# logic.net
KiCad netlist of a schematic drawn in EAGLE
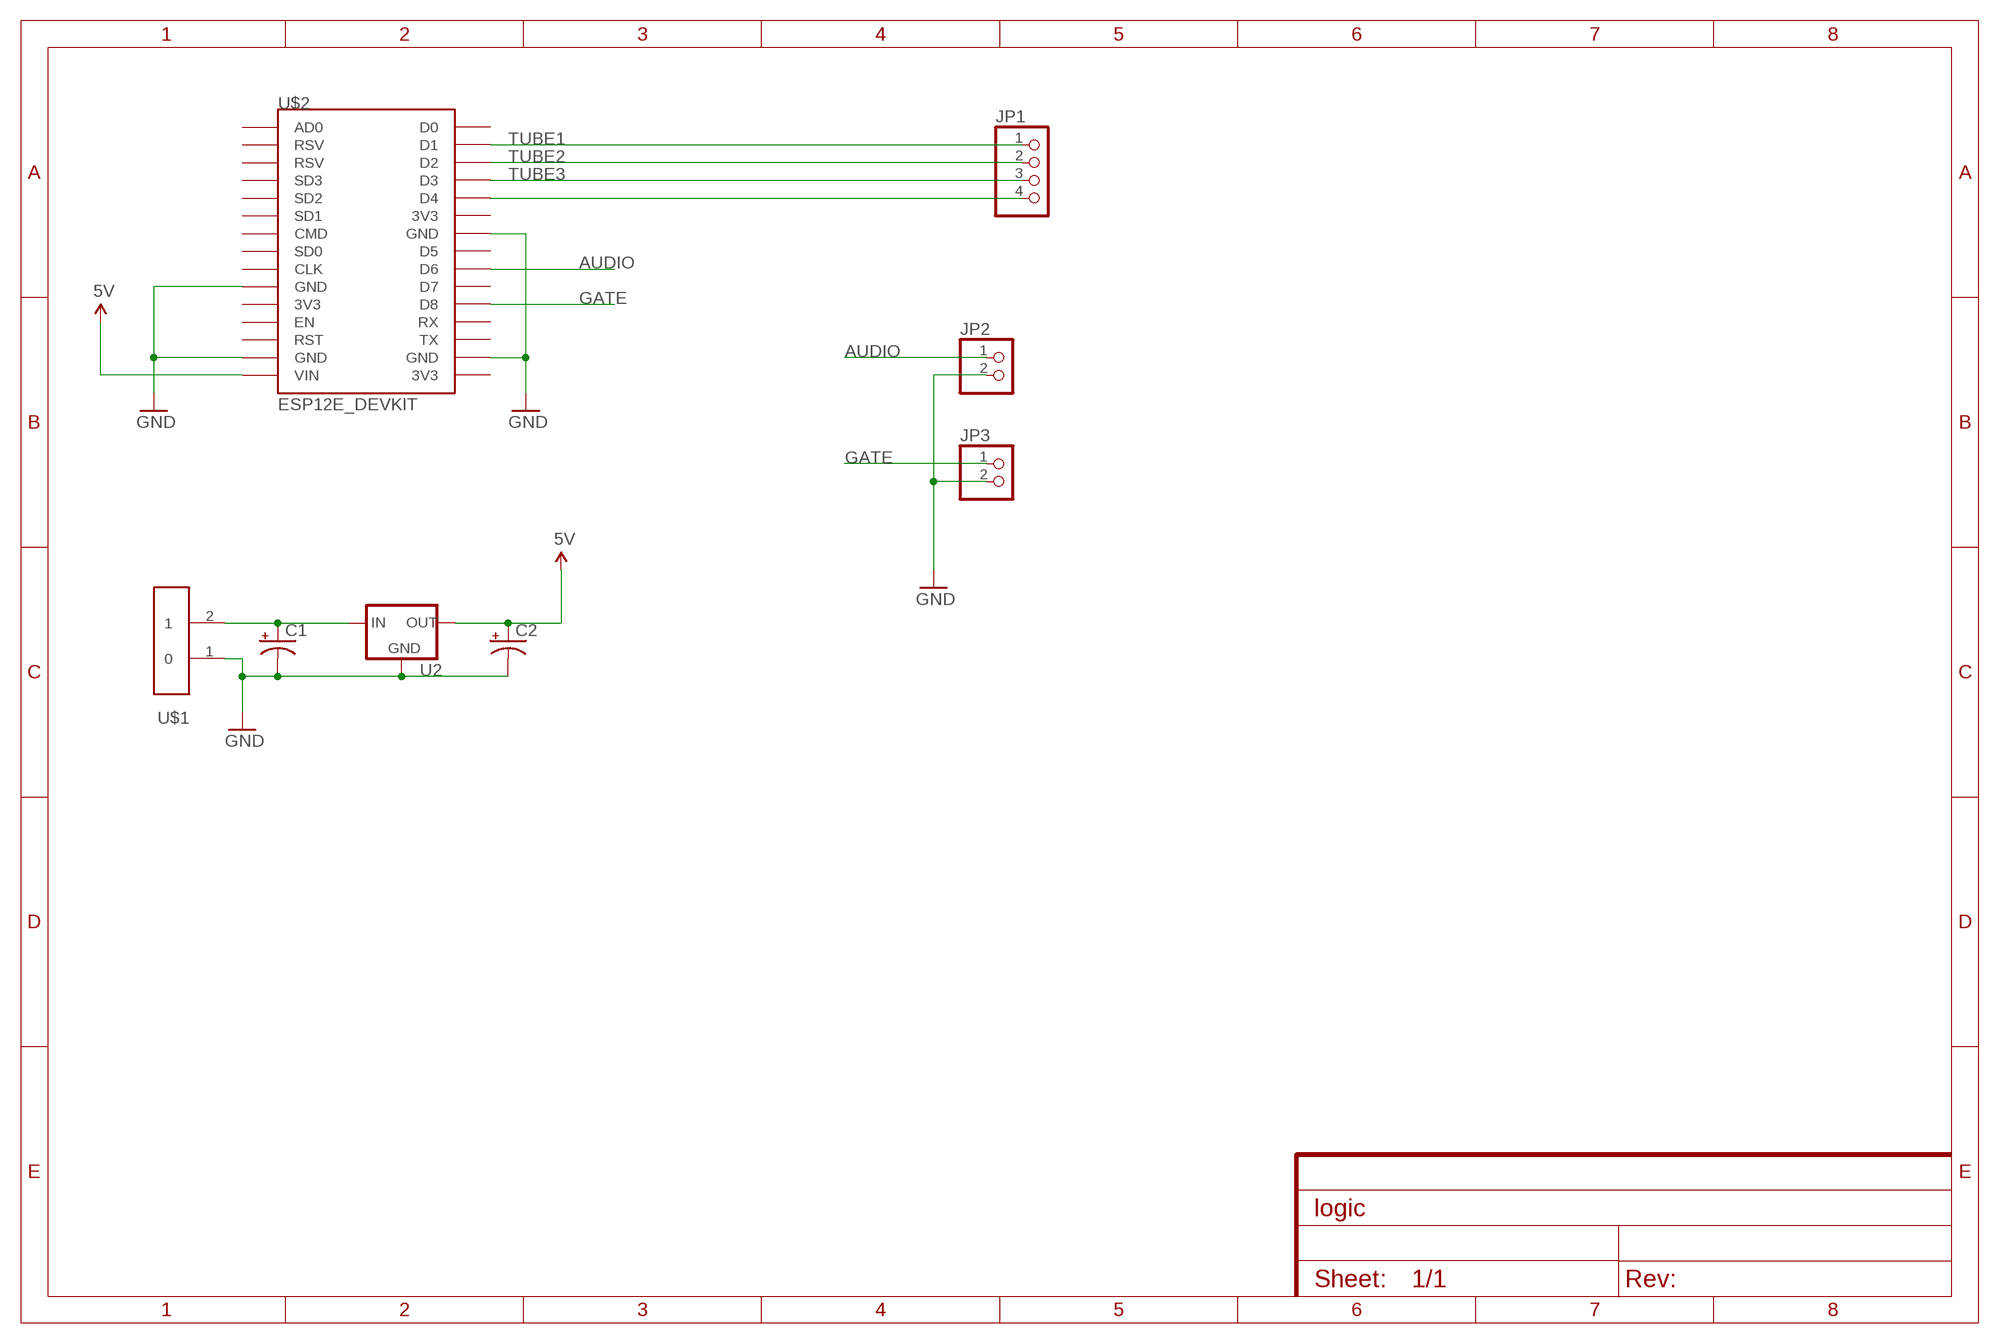
[diagram p0: schematic, sheet 1]

(export (version "E")
  (design (tool "Eeschema 10.0.6"))
  (components
    (comp (ref "C1")
      (value "10UF-25V-20%(PTH)")
      (footprint "eagle-import:CPOL-RADIAL-10UF-25V")
      (libsource (lib "eagle-import") (part "10UF-25V-20%(PTH)"))
    )
    (comp (ref "C2")
      (value "10UF-25V-20%(PTH)")
      (footprint "eagle-import:CPOL-RADIAL-10UF-25V")
      (libsource (lib "eagle-import") (part "10UF-25V-20%(PTH)"))
    )
    (comp (ref "JP1")
      (value "PINHD-1X4")
      (footprint "eagle-import:1X04")
      (libsource (lib "eagle-import") (part "PINHD-1X4"))
    )
    (comp (ref "JP2")
      (value "PINHD-1X2")
      (footprint "eagle-import:1X02")
      (libsource (lib "eagle-import") (part "PINHD-1X2"))
    )
    (comp (ref "JP3")
      (value "PINHD-1X2")
      (footprint "eagle-import:1X02")
      (libsource (lib "eagle-import") (part "PINHD-1X2"))
    )
    (comp (ref "U$1")
      (value "ED2609")
      (footprint "eagle-import:ED2609")
      (libsource (lib "eagle-import") (part "ED2609"))
    )
    (comp (ref "U$2")
      (value "ESP12E_DEVKIT")
      (footprint "eagle-import:ESP12E_DEVKIT")
      (libsource (lib "eagle-import") (part "ESP12E_DEVKIT"))
    )
    (comp (ref "U2")
      (value "V_REG_78XXSINK")
      (footprint "eagle-import:TO220-IGO")
      (libsource (lib "eagle-import") (part "V_REG_78XXSINK"))
    )
  )
  (nets
    (net (code "1") (name "/AUDIO") (class "Default")
      (node (ref "JP2") (pin "1") (pinfunction "1_1") (pintype "passive"))
      (node (ref "U$2") (pin "D6") (pinfunction "D6_D6") (pintype "bidirectional"))
    )
    (net (code "2") (name "/GATE") (class "Default")
      (node (ref "JP3") (pin "1") (pinfunction "1_1") (pintype "passive"))
      (node (ref "U$2") (pin "D8") (pinfunction "D8_D8") (pintype "bidirectional"))
    )
    (net (code "3") (name "/TUBE1") (class "Default")
      (node (ref "JP1") (pin "1") (pinfunction "1_1") (pintype "passive"))
      (node (ref "U$2") (pin "D1") (pinfunction "D1_D1") (pintype "bidirectional"))
    )
    (net (code "4") (name "/TUBE2") (class "Default")
      (node (ref "JP1") (pin "2") (pinfunction "2_2") (pintype "passive"))
      (node (ref "U$2") (pin "D2") (pinfunction "D2_D2") (pintype "bidirectional"))
    )
    (net (code "5") (name "/TUBE3") (class "Default")
      (node (ref "JP1") (pin "3") (pinfunction "3_3") (pintype "passive"))
      (node (ref "U$2") (pin "D3") (pinfunction "D3_D3") (pintype "bidirectional"))
    )
    (net (code "6") (name "5V") (class "Default")
      (node (ref "C2") (pin "1") (pinfunction "+_1") (pintype "passive"))
      (node (ref "U$2") (pin "VIN") (pinfunction "VIN_VIN") (pintype "bidirectional"))
      (node (ref "U2") (pin "OUT") (pinfunction "OUT_OUT") (pintype "passive"))
    )
    (net (code "7") (name "GND") (class "Default")
      (node (ref "C1") (pin "2") (pinfunction "-_2") (pintype "passive"))
      (node (ref "C2") (pin "2") (pinfunction "-_2") (pintype "passive"))
      (node (ref "JP2") (pin "2") (pinfunction "2_2") (pintype "passive"))
      (node (ref "JP3") (pin "2") (pinfunction "2_2") (pintype "passive"))
      (node (ref "U$1") (pin "1") (pinfunction "0_1") (pintype "bidirectional"))
      (node (ref "U$2") (pin "GND@0") (pinfunction "GND_GND@0") (pintype "bidirectional"))
      (node (ref "U$2") (pin "GND@1") (pinfunction "GND_GND@1") (pintype "bidirectional"))
      (node (ref "U$2") (pin "GND@2") (pinfunction "GND_GND@2") (pintype "bidirectional"))
      (node (ref "U$2") (pin "GND@3") (pinfunction "GND_GND@3") (pintype "bidirectional"))
      (node (ref "U2") (pin "GND") (pinfunction "GND_GND") (pintype "input"))
    )
    (net (code "8") (name "Net-(C1-+)") (class "Default")
      (node (ref "C1") (pin "1") (pinfunction "+_1") (pintype "passive"))
      (node (ref "U$1") (pin "2") (pinfunction "1_2") (pintype "bidirectional"))
      (node (ref "U2") (pin "IN") (pinfunction "IN_IN") (pintype "input"))
    )
    (net (code "9") (name "Net-(JP1-Pad4)") (class "Default")
      (node (ref "JP1") (pin "4") (pinfunction "4_4") (pintype "passive"))
      (node (ref "U$2") (pin "D4") (pinfunction "D4_D4") (pintype "bidirectional"))
    )
    (net (code "10") (name "unconnected-(U$2-3V3-Pad3V3@0)") (class "Default")
      (node (ref "U$2") (pin "3V3@0") (pinfunction "3V3_3V3@0") (pintype "bidirectional"))
    )
    (net (code "11") (name "unconnected-(U$2-3V3-Pad3V3@1)") (class "Default")
      (node (ref "U$2") (pin "3V3@1") (pinfunction "3V3_3V3@1") (pintype "bidirectional"))
    )
    (net (code "12") (name "unconnected-(U$2-3V3-Pad3V3@2)") (class "Default")
      (node (ref "U$2") (pin "3V3@2") (pinfunction "3V3_3V3@2") (pintype "bidirectional"))
    )
    (net (code "13") (name "unconnected-(U$2-PadAD0)") (class "Default")
      (node (ref "U$2") (pin "AD0") (pinfunction "AD0_AD0") (pintype "bidirectional"))
    )
    (net (code "14") (name "unconnected-(U$2-PadCLK)") (class "Default")
      (node (ref "U$2") (pin "CLK") (pinfunction "CLK_CLK") (pintype "bidirectional"))
    )
    (net (code "15") (name "unconnected-(U$2-PadCMD)") (class "Default")
      (node (ref "U$2") (pin "CMD") (pinfunction "CMD_CMD") (pintype "bidirectional"))
    )
    (net (code "16") (name "unconnected-(U$2-PadD0)") (class "Default")
      (node (ref "U$2") (pin "D0") (pinfunction "D0_D0") (pintype "bidirectional"))
    )
    (net (code "17") (name "unconnected-(U$2-PadD5)") (class "Default")
      (node (ref "U$2") (pin "D5") (pinfunction "D5_D5") (pintype "bidirectional"))
    )
    (net (code "18") (name "unconnected-(U$2-PadD7)") (class "Default")
      (node (ref "U$2") (pin "D7") (pinfunction "D7_D7") (pintype "bidirectional"))
    )
    (net (code "19") (name "unconnected-(U$2-PadEN)") (class "Default")
      (node (ref "U$2") (pin "EN") (pinfunction "EN_EN") (pintype "bidirectional"))
    )
    (net (code "20") (name "unconnected-(U$2-PadRST)") (class "Default")
      (node (ref "U$2") (pin "RST") (pinfunction "RST_RST") (pintype "bidirectional"))
    )
    (net (code "21") (name "unconnected-(U$2-PadRX)") (class "Default")
      (node (ref "U$2") (pin "RX") (pinfunction "RX_RX") (pintype "bidirectional"))
    )
    (net (code "22") (name "unconnected-(U$2-PadSD0)") (class "Default")
      (node (ref "U$2") (pin "SD0") (pinfunction "SD0_SD0") (pintype "bidirectional"))
    )
    (net (code "23") (name "unconnected-(U$2-PadSD1)") (class "Default")
      (node (ref "U$2") (pin "SD1") (pinfunction "SD1_SD1") (pintype "bidirectional"))
    )
    (net (code "24") (name "unconnected-(U$2-PadSD2)") (class "Default")
      (node (ref "U$2") (pin "SD2") (pinfunction "SD2_SD2") (pintype "bidirectional"))
    )
    (net (code "25") (name "unconnected-(U$2-PadSD3)") (class "Default")
      (node (ref "U$2") (pin "SD3") (pinfunction "SD3_SD3") (pintype "bidirectional"))
    )
    (net (code "26") (name "unconnected-(U$2-PadTX)") (class "Default")
      (node (ref "U$2") (pin "TX") (pinfunction "TX_TX") (pintype "bidirectional"))
    )
    (net (code "27") (name "unconnected-(U$2-RSV-PadRSV@0)") (class "Default")
      (node (ref "U$2") (pin "RSV@0") (pinfunction "RSV_RSV@0") (pintype "bidirectional"))
    )
    (net (code "28") (name "unconnected-(U$2-RSV-PadRSV@1)") (class "Default")
      (node (ref "U$2") (pin "RSV@1") (pinfunction "RSV_RSV@1") (pintype "bidirectional"))
    )
  )
)
